# tick-display-mk-6.net
KiCad netlist of a schematic drawn in EAGLE
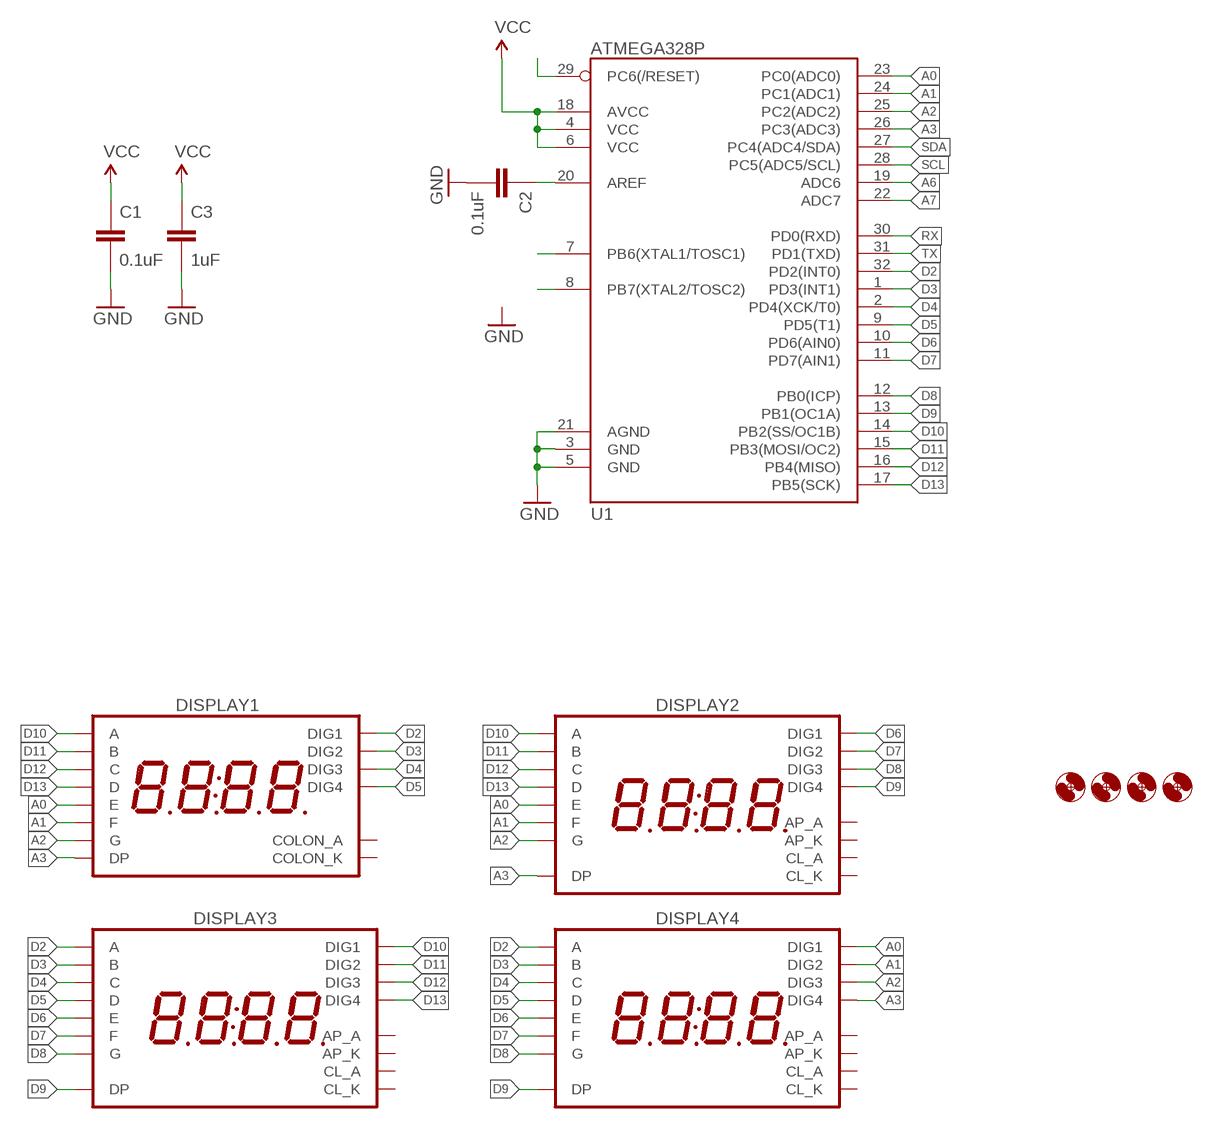
[diagram p0: schematic, sheet 1]

(export (version "E")
  (design (tool "Eeschema 10.0.6"))
  (components
    (comp (ref "C1")
      (value "0.1uF")
      (footprint "eagle-import:C0603")
      (libsource (lib "eagle-import") (part "CAPACITOR-CERAMICC0603"))
    )
    (comp (ref "C2")
      (value "0.1uF")
      (footprint "eagle-import:C0603")
      (libsource (lib "eagle-import") (part "CAPACITOR-CERAMICC0603"))
    )
    (comp (ref "C3")
      (value "1uF")
      (footprint "eagle-import:C0805")
      (libsource (lib "eagle-import") (part "CAPACITOR-CERAMICC0805"))
    )
    (comp (ref "DISPLAY1")
      (value "7SEG_4DIGIT_COLON14.2MM-CC")
      (footprint "eagle-import:7SEG_4DIG_0.56IN_14MM_ADAFRUIT")
      (libsource (lib "eagle-import") (part "7SEG_4DIGIT_COLON14.2MM-CC"))
    )
    (comp (ref "DISPLAY2")
      (value "7SEG_4DIGIT_COLON_APOS")
      (footprint "eagle-import:7SEG_4DIG_10MM")
      (libsource (lib "eagle-import") (part "7SEG_4DIGIT_COLON_APOS"))
    )
    (comp (ref "DISPLAY3")
      (value "7SEG_4DIGIT_COLON_APOS")
      (footprint "eagle-import:7SEG_4DIG_10MM")
      (libsource (lib "eagle-import") (part "7SEG_4DIGIT_COLON_APOS"))
    )
    (comp (ref "DISPLAY4")
      (value "7SEG_4DIGIT_COLON_APOS")
      (footprint "eagle-import:7SEG_4DIG_10MM")
      (libsource (lib "eagle-import") (part "7SEG_4DIGIT_COLON_APOS"))
    )
    (comp (ref "H1")
      (value "HOLE#2")
      (footprint "eagle-import:HOLE-#2")
      (libsource (lib "eagle-import") (part "HOLE#2"))
    )
    (comp (ref "H2")
      (value "HOLE#2")
      (footprint "eagle-import:HOLE-#2")
      (libsource (lib "eagle-import") (part "HOLE#2"))
    )
    (comp (ref "H3")
      (value "HOLE#2")
      (footprint "eagle-import:HOLE-#2")
      (libsource (lib "eagle-import") (part "HOLE#2"))
    )
    (comp (ref "H4")
      (value "HOLE#2")
      (footprint "eagle-import:HOLE-#2")
      (libsource (lib "eagle-import") (part "HOLE#2"))
    )
    (comp (ref "U1")
      (value "ATMEGA328P")
      (footprint "eagle-import:TQFP32-08")
      (libsource (lib "eagle-import") (part "ATMEGA328_SMT"))
    )
  )
  (nets
    (net (code "1") (name "A0") (class "Default")
      (node (ref "DISPLAY1") (pin "P$1") (pinfunction "E_P$1") (pintype "passive"))
      (node (ref "DISPLAY2") (pin "5") (pinfunction "E_5") (pintype "passive"))
      (node (ref "DISPLAY4") (pin "1") (pinfunction "DIG1_1") (pintype "passive"))
      (node (ref "U1") (pin "23") (pinfunction "PC0(ADC0)_23") (pintype "bidirectional"))
    )
    (net (code "2") (name "A1") (class "Default")
      (node (ref "DISPLAY1") (pin "P$12") (pinfunction "F_P$12") (pintype "passive"))
      (node (ref "DISPLAY2") (pin "11") (pinfunction "F_11") (pintype "passive"))
      (node (ref "DISPLAY4") (pin "2") (pinfunction "DIG2_2") (pintype "passive"))
      (node (ref "U1") (pin "24") (pinfunction "PC1(ADC1)_24") (pintype "bidirectional"))
    )
    (net (code "3") (name "A2") (class "Default")
      (node (ref "DISPLAY1") (pin "P$5") (pinfunction "G_P$5") (pintype "passive"))
      (node (ref "DISPLAY2") (pin "15") (pinfunction "G_15") (pintype "passive"))
      (node (ref "DISPLAY4") (pin "6") (pinfunction "DIG3_6") (pintype "passive"))
      (node (ref "U1") (pin "25") (pinfunction "PC2(ADC2)_25") (pintype "bidirectional"))
    )
    (net (code "4") (name "A3") (class "Default")
      (node (ref "DISPLAY1") (pin "P$3") (pinfunction "DP_P$3") (pintype "passive"))
      (node (ref "DISPLAY2") (pin "7") (pinfunction "DP_7") (pintype "passive"))
      (node (ref "DISPLAY4") (pin "8") (pinfunction "DIG4_8") (pintype "passive"))
      (node (ref "U1") (pin "26") (pinfunction "PC3(ADC3)_26") (pintype "bidirectional"))
    )
    (net (code "5") (name "A6") (class "Default")
      (node (ref "U1") (pin "19") (pinfunction "ADC6_19") (pintype "bidirectional"))
    )
    (net (code "6") (name "A7") (class "Default")
      (node (ref "U1") (pin "22") (pinfunction "ADC7_22") (pintype "bidirectional"))
    )
    (net (code "7") (name "D2") (class "Default")
      (node (ref "DISPLAY1") (pin "P$14") (pinfunction "DIG1_P$14") (pintype "passive"))
      (node (ref "DISPLAY3") (pin "14") (pinfunction "A_14") (pintype "passive"))
      (node (ref "DISPLAY4") (pin "14") (pinfunction "A_14") (pintype "passive"))
      (node (ref "U1") (pin "32") (pinfunction "PD2(INT0)_32") (pintype "bidirectional"))
    )
    (net (code "8") (name "D3") (class "Default")
      (node (ref "DISPLAY1") (pin "P$11") (pinfunction "DIG2_P$11") (pintype "passive"))
      (node (ref "DISPLAY3") (pin "16") (pinfunction "B_16") (pintype "passive"))
      (node (ref "DISPLAY4") (pin "16") (pinfunction "B_16") (pintype "passive"))
      (node (ref "U1") (pin "1") (pinfunction "PD3(INT1)_1") (pintype "bidirectional"))
    )
    (net (code "9") (name "D4") (class "Default")
      (node (ref "DISPLAY1") (pin "P$10") (pinfunction "DIG3_P$10") (pintype "passive"))
      (node (ref "DISPLAY3") (pin "13") (pinfunction "C_13") (pintype "passive"))
      (node (ref "DISPLAY4") (pin "13") (pinfunction "C_13") (pintype "passive"))
      (node (ref "U1") (pin "2") (pinfunction "PD4(XCK/T0)_2") (pintype "bidirectional"))
    )
    (net (code "10") (name "D5") (class "Default")
      (node (ref "DISPLAY1") (pin "P$6") (pinfunction "DIG4_P$6") (pintype "passive"))
      (node (ref "DISPLAY3") (pin "3") (pinfunction "D_3") (pintype "passive"))
      (node (ref "DISPLAY4") (pin "3") (pinfunction "D_3") (pintype "passive"))
      (node (ref "U1") (pin "9") (pinfunction "PD5(T1)_9") (pintype "bidirectional"))
    )
    (net (code "11") (name "D6") (class "Default")
      (node (ref "DISPLAY2") (pin "1") (pinfunction "DIG1_1") (pintype "passive"))
      (node (ref "DISPLAY3") (pin "5") (pinfunction "E_5") (pintype "passive"))
      (node (ref "DISPLAY4") (pin "5") (pinfunction "E_5") (pintype "passive"))
      (node (ref "U1") (pin "10") (pinfunction "PD6(AIN0)_10") (pintype "bidirectional"))
    )
    (net (code "12") (name "D7") (class "Default")
      (node (ref "DISPLAY2") (pin "2") (pinfunction "DIG2_2") (pintype "passive"))
      (node (ref "DISPLAY3") (pin "11") (pinfunction "F_11") (pintype "passive"))
      (node (ref "DISPLAY4") (pin "11") (pinfunction "F_11") (pintype "passive"))
      (node (ref "U1") (pin "11") (pinfunction "PD7(AIN1)_11") (pintype "bidirectional"))
    )
    (net (code "13") (name "D8") (class "Default")
      (node (ref "DISPLAY2") (pin "6") (pinfunction "DIG3_6") (pintype "passive"))
      (node (ref "DISPLAY3") (pin "15") (pinfunction "G_15") (pintype "passive"))
      (node (ref "DISPLAY4") (pin "15") (pinfunction "G_15") (pintype "passive"))
      (node (ref "U1") (pin "12") (pinfunction "PB0(ICP)_12") (pintype "bidirectional"))
    )
    (net (code "14") (name "D9") (class "Default")
      (node (ref "DISPLAY2") (pin "8") (pinfunction "DIG4_8") (pintype "passive"))
      (node (ref "DISPLAY3") (pin "7") (pinfunction "DP_7") (pintype "passive"))
      (node (ref "DISPLAY4") (pin "7") (pinfunction "DP_7") (pintype "passive"))
      (node (ref "U1") (pin "13") (pinfunction "PB1(OC1A)_13") (pintype "bidirectional"))
    )
    (net (code "15") (name "D10") (class "Default")
      (node (ref "DISPLAY1") (pin "P$13") (pinfunction "A_P$13") (pintype "passive"))
      (node (ref "DISPLAY2") (pin "14") (pinfunction "A_14") (pintype "passive"))
      (node (ref "DISPLAY3") (pin "1") (pinfunction "DIG1_1") (pintype "passive"))
      (node (ref "U1") (pin "14") (pinfunction "PB2(SS/OC1B)_14") (pintype "bidirectional"))
    )
    (net (code "16") (name "D11") (class "Default")
      (node (ref "DISPLAY1") (pin "P$9") (pinfunction "B_P$9") (pintype "passive"))
      (node (ref "DISPLAY2") (pin "16") (pinfunction "B_16") (pintype "passive"))
      (node (ref "DISPLAY3") (pin "2") (pinfunction "DIG2_2") (pintype "passive"))
      (node (ref "U1") (pin "15") (pinfunction "PB3(MOSI/OC2)_15") (pintype "bidirectional"))
    )
    (net (code "17") (name "D12") (class "Default")
      (node (ref "DISPLAY1") (pin "P$4") (pinfunction "C_P$4") (pintype "passive"))
      (node (ref "DISPLAY2") (pin "13") (pinfunction "C_13") (pintype "passive"))
      (node (ref "DISPLAY3") (pin "6") (pinfunction "DIG3_6") (pintype "passive"))
      (node (ref "U1") (pin "16") (pinfunction "PB4(MISO)_16") (pintype "bidirectional"))
    )
    (net (code "18") (name "D13") (class "Default")
      (node (ref "DISPLAY1") (pin "P$2") (pinfunction "D_P$2") (pintype "passive"))
      (node (ref "DISPLAY2") (pin "3") (pinfunction "D_3") (pintype "passive"))
      (node (ref "DISPLAY3") (pin "8") (pinfunction "DIG4_8") (pintype "passive"))
      (node (ref "U1") (pin "17") (pinfunction "PB5(SCK)_17") (pintype "bidirectional"))
    )
    (net (code "19") (name "GND") (class "Default")
      (node (ref "C1") (pin "2") (pinfunction "2_2") (pintype "passive"))
      (node (ref "C2") (pin "2") (pinfunction "2_2") (pintype "passive"))
      (node (ref "C3") (pin "2") (pinfunction "2_2") (pintype "passive"))
      (node (ref "U1") (pin "21") (pinfunction "AGND_21") (pintype "bidirectional"))
      (node (ref "U1") (pin "3") (pinfunction "GND_3") (pintype "bidirectional"))
      (node (ref "U1") (pin "5") (pinfunction "GND_5") (pintype "bidirectional"))
    )
    (net (code "20") (name "Net-(U1-AREF)") (class "Default")
      (node (ref "C2") (pin "1") (pinfunction "1_1") (pintype "passive"))
      (node (ref "U1") (pin "20") (pinfunction "AREF_20") (pintype "bidirectional"))
    )
    (net (code "21") (name "RX") (class "Default")
      (node (ref "U1") (pin "30") (pinfunction "PD0(RXD)_30") (pintype "bidirectional"))
    )
    (net (code "22") (name "SCL") (class "Default")
      (node (ref "U1") (pin "28") (pinfunction "PC5(ADC5/SCL)_28") (pintype "bidirectional"))
    )
    (net (code "23") (name "SDA") (class "Default")
      (node (ref "U1") (pin "27") (pinfunction "PC4(ADC4/SDA)_27") (pintype "bidirectional"))
    )
    (net (code "24") (name "TX") (class "Default")
      (node (ref "U1") (pin "31") (pinfunction "PD1(TXD)_31") (pintype "bidirectional"))
    )
    (net (code "25") (name "VCC") (class "Default")
      (node (ref "C1") (pin "1") (pinfunction "1_1") (pintype "passive"))
      (node (ref "C3") (pin "1") (pinfunction "1_1") (pintype "passive"))
      (node (ref "U1") (pin "18") (pinfunction "AVCC_18") (pintype "bidirectional"))
      (node (ref "U1") (pin "4") (pinfunction "VCC_4") (pintype "bidirectional"))
      (node (ref "U1") (pin "6") (pinfunction "VCC_6") (pintype "bidirectional"))
    )
    (net (code "26") (name "unconnected-(DISPLAY1-COLON_A-PadP$8)") (class "Default")
      (node (ref "DISPLAY1") (pin "P$8") (pinfunction "COLON_A_P$8") (pintype "passive"))
    )
    (net (code "27") (name "unconnected-(DISPLAY1-COLON_K-PadP$7)") (class "Default")
      (node (ref "DISPLAY1") (pin "P$7") (pinfunction "COLON_K_P$7") (pintype "passive"))
    )
    (net (code "28") (name "unconnected-(DISPLAY2-AP_A-Pad10)") (class "Default")
      (node (ref "DISPLAY2") (pin "10") (pinfunction "AP_A_10") (pintype "bidirectional"))
    )
    (net (code "29") (name "unconnected-(DISPLAY2-AP_K-Pad9)") (class "Default")
      (node (ref "DISPLAY2") (pin "9") (pinfunction "AP_K_9") (pintype "bidirectional"))
    )
    (net (code "30") (name "unconnected-(DISPLAY2-CL_A-Pad4)") (class "Default")
      (node (ref "DISPLAY2") (pin "4") (pinfunction "CL_A_4") (pintype "passive"))
    )
    (net (code "31") (name "unconnected-(DISPLAY2-CL_K-Pad12)") (class "Default")
      (node (ref "DISPLAY2") (pin "12") (pinfunction "CL_K_12") (pintype "passive"))
    )
    (net (code "32") (name "unconnected-(DISPLAY3-AP_A-Pad10)") (class "Default")
      (node (ref "DISPLAY3") (pin "10") (pinfunction "AP_A_10") (pintype "bidirectional"))
    )
    (net (code "33") (name "unconnected-(DISPLAY3-AP_K-Pad9)") (class "Default")
      (node (ref "DISPLAY3") (pin "9") (pinfunction "AP_K_9") (pintype "bidirectional"))
    )
    (net (code "34") (name "unconnected-(DISPLAY3-CL_A-Pad4)") (class "Default")
      (node (ref "DISPLAY3") (pin "4") (pinfunction "CL_A_4") (pintype "passive"))
    )
    (net (code "35") (name "unconnected-(DISPLAY3-CL_K-Pad12)") (class "Default")
      (node (ref "DISPLAY3") (pin "12") (pinfunction "CL_K_12") (pintype "passive"))
    )
    (net (code "36") (name "unconnected-(DISPLAY4-AP_A-Pad10)") (class "Default")
      (node (ref "DISPLAY4") (pin "10") (pinfunction "AP_A_10") (pintype "bidirectional"))
    )
    (net (code "37") (name "unconnected-(DISPLAY4-AP_K-Pad9)") (class "Default")
      (node (ref "DISPLAY4") (pin "9") (pinfunction "AP_K_9") (pintype "bidirectional"))
    )
    (net (code "38") (name "unconnected-(DISPLAY4-CL_A-Pad4)") (class "Default")
      (node (ref "DISPLAY4") (pin "4") (pinfunction "CL_A_4") (pintype "passive"))
    )
    (net (code "39") (name "unconnected-(DISPLAY4-CL_K-Pad12)") (class "Default")
      (node (ref "DISPLAY4") (pin "12") (pinfunction "CL_K_12") (pintype "passive"))
    )
    (net (code "40") (name "unconnected-(U1-PB6(XTAL1{slash}TOSC1)-Pad7)") (class "Default")
      (node (ref "U1") (pin "7") (pinfunction "PB6(XTAL1/TOSC1)_7") (pintype "bidirectional"))
    )
    (net (code "41") (name "unconnected-(U1-PB7(XTAL2{slash}TOSC2)-Pad8)") (class "Default")
      (node (ref "U1") (pin "8") (pinfunction "PB7(XTAL2/TOSC2)_8") (pintype "bidirectional"))
    )
    (net (code "42") (name "unconnected-(U1-PC6({slash}RESET)-Pad29)") (class "Default")
      (node (ref "U1") (pin "29") (pinfunction "PC6(/RESET)_29") (pintype "bidirectional"))
    )
  )
)
